# lolo4-rc2.net
KiCad netlist of a schematic drawn in EAGLE
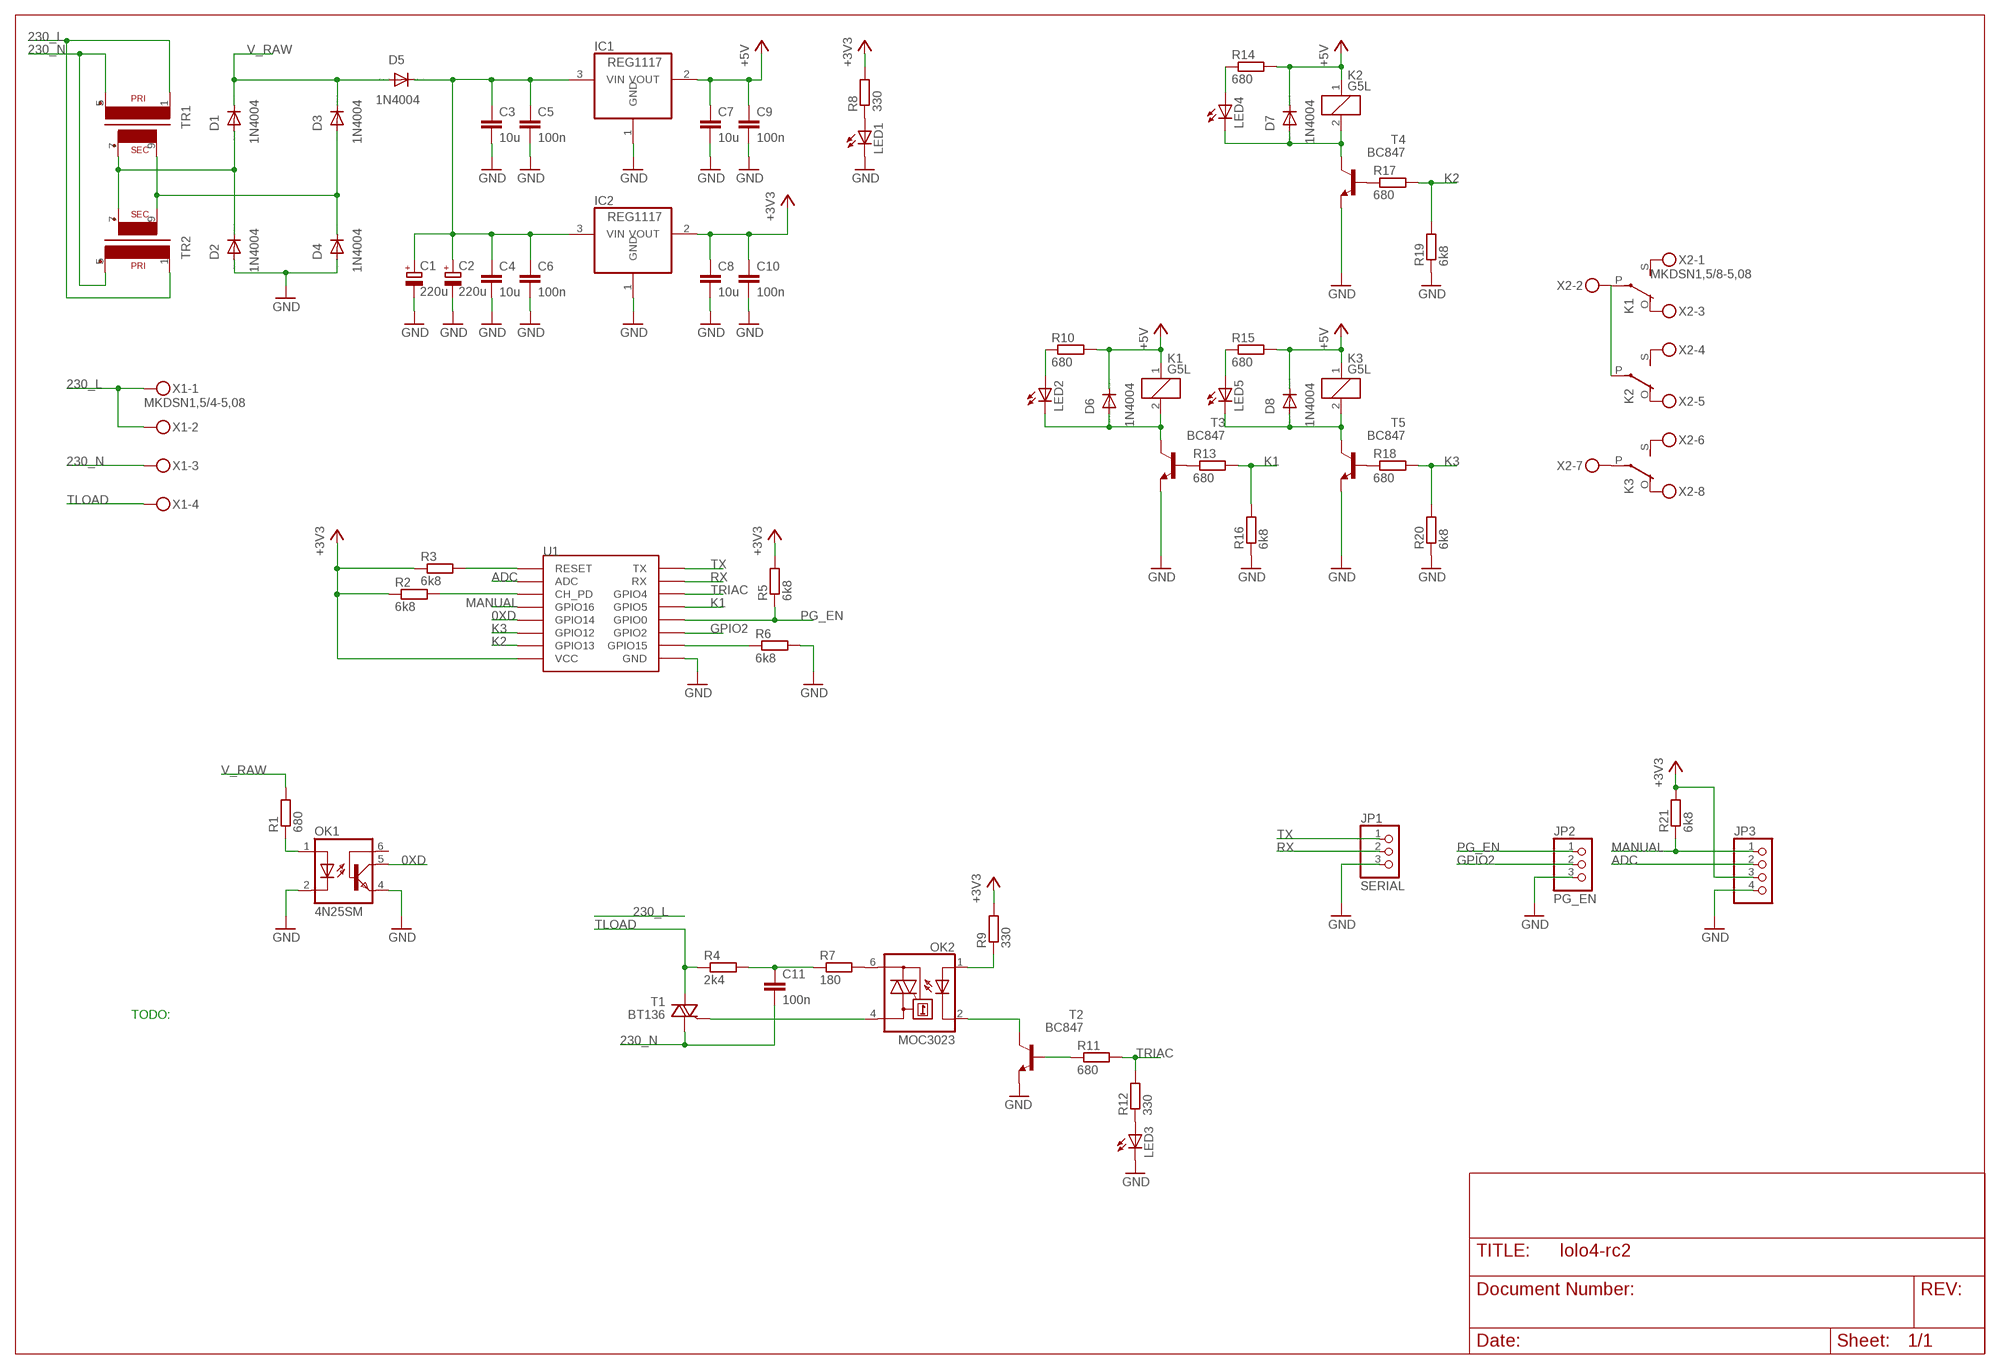
[diagram p0: schematic, sheet 1]

(export (version "E")
  (design (tool "Eeschema 10.0.6"))
  (components
    (comp (ref "C1")
      (value "220u")
      (footprint "eagle-import:SANYO-OSCON_SMD_E7")
      (libsource (lib "eagle-import") (part "CPOL-EUSANYO_SMD_E7"))
    )
    (comp (ref "C2")
      (value "220u")
      (footprint "eagle-import:SANYO-OSCON_SMD_E7")
      (libsource (lib "eagle-import") (part "CPOL-EUSANYO_SMD_E7"))
    )
    (comp (ref "C3")
      (value "10u")
      (footprint "eagle-import:C1206")
      (libsource (lib "eagle-import") (part "resistor_C-EUC1206"))
    )
    (comp (ref "C4")
      (value "10u")
      (footprint "eagle-import:C1206")
      (libsource (lib "eagle-import") (part "resistor_C-EUC1206"))
    )
    (comp (ref "C5")
      (value "100n")
      (footprint "eagle-import:C1206")
      (libsource (lib "eagle-import") (part "resistor_C-EUC1206"))
    )
    (comp (ref "C6")
      (value "100n")
      (footprint "eagle-import:C1206")
      (libsource (lib "eagle-import") (part "resistor_C-EUC1206"))
    )
    (comp (ref "C7")
      (value "10u")
      (footprint "eagle-import:C1206")
      (libsource (lib "eagle-import") (part "resistor_C-EUC1206"))
    )
    (comp (ref "C8")
      (value "10u")
      (footprint "eagle-import:C1206")
      (libsource (lib "eagle-import") (part "resistor_C-EUC1206"))
    )
    (comp (ref "C9")
      (value "100n")
      (footprint "eagle-import:C1206")
      (libsource (lib "eagle-import") (part "resistor_C-EUC1206"))
    )
    (comp (ref "C10")
      (value "100n")
      (footprint "eagle-import:C1206")
      (libsource (lib "eagle-import") (part "resistor_C-EUC1206"))
    )
    (comp (ref "C11")
      (value "100n")
      (footprint "eagle-import:C150-054X183")
      (libsource (lib "eagle-import") (part "C-EU150-054X183"))
    )
    (comp (ref "D1")
      (value "1N4004")
      (footprint "eagle-import:DO41-10")
      (libsource (lib "eagle-import") (part "1N4004"))
    )
    (comp (ref "D2")
      (value "1N4004")
      (footprint "eagle-import:DO41-10")
      (libsource (lib "eagle-import") (part "1N4004"))
    )
    (comp (ref "D3")
      (value "1N4004")
      (footprint "eagle-import:DO41-10")
      (libsource (lib "eagle-import") (part "1N4004"))
    )
    (comp (ref "D4")
      (value "1N4004")
      (footprint "eagle-import:DO41-10")
      (libsource (lib "eagle-import") (part "1N4004"))
    )
    (comp (ref "D5")
      (value "1N4004")
      (footprint "eagle-import:DO41-10")
      (libsource (lib "eagle-import") (part "1N4004"))
    )
    (comp (ref "D6")
      (value "1N4004")
      (footprint "eagle-import:DO41-10")
      (libsource (lib "eagle-import") (part "1N4004"))
    )
    (comp (ref "D7")
      (value "1N4004")
      (footprint "eagle-import:DO41-10")
      (libsource (lib "eagle-import") (part "1N4004"))
    )
    (comp (ref "D8")
      (value "1N4004")
      (footprint "eagle-import:DO41-10")
      (libsource (lib "eagle-import") (part "1N4004"))
    )
    (comp (ref "IC1")
      (value "REG1117")
      (footprint "eagle-import:SOT223")
      (libsource (lib "eagle-import") (part "REG1117"))
    )
    (comp (ref "IC2")
      (value "REG1117")
      (footprint "eagle-import:SOT223")
      (libsource (lib "eagle-import") (part "REG1117"))
    )
    (comp (ref "JP1")
      (value "SERIAL")
      (footprint "eagle-import:1X03")
      (libsource (lib "eagle-import") (part "PINHD-1X3"))
    )
    (comp (ref "JP2")
      (value "PG_EN")
      (footprint "eagle-import:1X03")
      (libsource (lib "eagle-import") (part "PINHD-1X3"))
    )
    (comp (ref "JP3")
      (value "PINHD-1X4")
      (footprint "eagle-import:1X04")
      (libsource (lib "eagle-import") (part "PINHD-1X4"))
    )
    (comp (ref "K1")
      (value "G5L")
      (footprint "eagle-import:G5LE")
      (libsource (lib "eagle-import") (part "G5L"))
    )
    (comp (ref "K2")
      (value "G5L")
      (footprint "eagle-import:G5LE")
      (libsource (lib "eagle-import") (part "G5L"))
    )
    (comp (ref "K3")
      (value "G5L")
      (footprint "eagle-import:G5LE")
      (libsource (lib "eagle-import") (part "G5L"))
    )
    (comp (ref "LED1")
      (value "LEDSML1206")
      (footprint "eagle-import:SML1206")
      (libsource (lib "eagle-import") (part "LEDSML1206"))
    )
    (comp (ref "LED2")
      (value "LEDSML1206")
      (footprint "eagle-import:SML1206")
      (libsource (lib "eagle-import") (part "LEDSML1206"))
    )
    (comp (ref "LED3")
      (value "LEDSML1206")
      (footprint "eagle-import:SML1206")
      (libsource (lib "eagle-import") (part "LEDSML1206"))
    )
    (comp (ref "LED4")
      (value "LEDSML1206")
      (footprint "eagle-import:SML1206")
      (libsource (lib "eagle-import") (part "LEDSML1206"))
    )
    (comp (ref "LED5")
      (value "LEDSML1206")
      (footprint "eagle-import:SML1206")
      (libsource (lib "eagle-import") (part "LEDSML1206"))
    )
    (comp (ref "OK1")
      (value "4N25SM")
      (footprint "eagle-import:DIL6-SMD")
      (fields (field (name "MF") "FAIRCHILD SEMICONDUCTOR"))
      (libsource (lib "eagle-import") (part "4N?MS25"))
    )
    (comp (ref "OK2")
      (value "MOC3023")
      (footprint "eagle-import:DIL6-SMD")
      (fields (field (name "MF") "FAIRCHILD SEMICONDUCTOR") (field (name "MPN") "MOC3031SM"))
      (libsource (lib "eagle-import") (part "MOC30S31"))
    )
    (comp (ref "R1")
      (value "680")
      (footprint "eagle-import:R1206")
      (libsource (lib "eagle-import") (part "R-EU_R1206"))
    )
    (comp (ref "R2")
      (value "6k8")
      (footprint "eagle-import:R1206")
      (libsource (lib "eagle-import") (part "R-EU_R1206"))
    )
    (comp (ref "R3")
      (value "6k8")
      (footprint "eagle-import:R1206")
      (libsource (lib "eagle-import") (part "R-EU_R1206"))
    )
    (comp (ref "R4")
      (value "2k4")
      (footprint "eagle-import:0207_7")
      (libsource (lib "eagle-import") (part "R-EU_0207/7"))
    )
    (comp (ref "R5")
      (value "6k8")
      (footprint "eagle-import:R1206")
      (libsource (lib "eagle-import") (part "R-EU_R1206"))
    )
    (comp (ref "R6")
      (value "6k8")
      (footprint "eagle-import:R1206")
      (libsource (lib "eagle-import") (part "R-EU_R1206"))
    )
    (comp (ref "R7")
      (value "180")
      (footprint "eagle-import:0207_7")
      (libsource (lib "eagle-import") (part "R-EU_0207/7"))
    )
    (comp (ref "R8")
      (value "330")
      (footprint "eagle-import:R1206")
      (libsource (lib "eagle-import") (part "R-EU_R1206"))
    )
    (comp (ref "R9")
      (value "330")
      (footprint "eagle-import:R1206")
      (libsource (lib "eagle-import") (part "R-EU_R1206"))
    )
    (comp (ref "R10")
      (value "680")
      (footprint "eagle-import:R1206")
      (libsource (lib "eagle-import") (part "R-EU_R1206"))
    )
    (comp (ref "R11")
      (value "680")
      (footprint "eagle-import:R1206")
      (libsource (lib "eagle-import") (part "R-EU_R1206"))
    )
    (comp (ref "R12")
      (value "330")
      (footprint "eagle-import:R1206")
      (libsource (lib "eagle-import") (part "R-EU_R1206"))
    )
    (comp (ref "R13")
      (value "680")
      (footprint "eagle-import:R1206")
      (libsource (lib "eagle-import") (part "R-EU_R1206"))
    )
    (comp (ref "R14")
      (value "680")
      (footprint "eagle-import:R1206")
      (libsource (lib "eagle-import") (part "R-EU_R1206"))
    )
    (comp (ref "R15")
      (value "680")
      (footprint "eagle-import:R1206")
      (libsource (lib "eagle-import") (part "R-EU_R1206"))
    )
    (comp (ref "R16")
      (value "6k8")
      (footprint "eagle-import:R1206")
      (libsource (lib "eagle-import") (part "R-EU_R1206"))
    )
    (comp (ref "R17")
      (value "680")
      (footprint "eagle-import:R1206")
      (libsource (lib "eagle-import") (part "R-EU_R1206"))
    )
    (comp (ref "R18")
      (value "680")
      (footprint "eagle-import:R1206")
      (libsource (lib "eagle-import") (part "R-EU_R1206"))
    )
    (comp (ref "R19")
      (value "6k8")
      (footprint "eagle-import:R1206")
      (libsource (lib "eagle-import") (part "R-EU_R1206"))
    )
    (comp (ref "R20")
      (value "6k8")
      (footprint "eagle-import:R1206")
      (libsource (lib "eagle-import") (part "R-EU_R1206"))
    )
    (comp (ref "R21")
      (value "6k8")
      (footprint "eagle-import:R1206")
      (libsource (lib "eagle-import") (part "R-EU_R1206"))
    )
    (comp (ref "T1")
      (value "BT136")
      (footprint "eagle-import:TO220AB")
      (libsource (lib "eagle-import") (part "BT136"))
    )
    (comp (ref "T2")
      (value "BC847")
      (footprint "eagle-import:SOT23")
      (libsource (lib "eagle-import") (part "BC847"))
    )
    (comp (ref "T3")
      (value "BC847")
      (footprint "eagle-import:SOT23")
      (libsource (lib "eagle-import") (part "BC847"))
    )
    (comp (ref "T4")
      (value "BC847")
      (footprint "eagle-import:SOT23")
      (libsource (lib "eagle-import") (part "BC847"))
    )
    (comp (ref "T5")
      (value "BC847")
      (footprint "eagle-import:SOT23")
      (libsource (lib "eagle-import") (part "BC847"))
    )
    (comp (ref "TR1")
      (value "VR11")
      (footprint "eagle-import:VR11")
      (libsource (lib "eagle-import") (part "VR11"))
    )
    (comp (ref "TR2")
      (value "VR11")
      (footprint "eagle-import:VR11")
      (libsource (lib "eagle-import") (part "VR11"))
    )
    (comp (ref "U1")
      (value "ESP12SMD")
      (footprint "eagle-import:ESP12-SMD")
      (libsource (lib "eagle-import") (part "ESP12SMD"))
    )
    (comp (ref "X1")
      (value "MKDSN1,5/4-5,08")
      (footprint "eagle-import:MKDSN1,5_4-5,08")
      (libsource (lib "eagle-import") (part "MKDSN1,5/4-5,08"))
    )
    (comp (ref "X2")
      (value "MKDSN1,5/8-5,08")
      (footprint "eagle-import:MKDSN1,5_8-5,08")
      (libsource (lib "eagle-import") (part "MKDSN1,5/8-5,08"))
    )
  )
  (nets
    (net (code "1") (name "+3V3") (class "Default")
      (node (ref "C10") (pin "1") (pinfunction "1_1") (pintype "passive"))
      (node (ref "C8") (pin "1") (pinfunction "1_1") (pintype "passive"))
      (node (ref "IC2") (pin "2") (pinfunction "VOUT_2") (pintype "output"))
      (node (ref "JP3") (pin "3") (pinfunction "3_3") (pintype "passive"))
      (node (ref "R2") (pin "1") (pinfunction "1_1") (pintype "passive"))
      (node (ref "R21") (pin "2") (pinfunction "2_2") (pintype "passive"))
      (node (ref "R3") (pin "1") (pinfunction "1_1") (pintype "passive"))
      (node (ref "R5") (pin "2") (pinfunction "2_2") (pintype "passive"))
      (node (ref "R8") (pin "2") (pinfunction "2_2") (pintype "passive"))
      (node (ref "R9") (pin "2") (pinfunction "2_2") (pintype "passive"))
      (node (ref "U1") (pin "VCC") (pinfunction "VCC_VCC") (pintype "bidirectional"))
    )
    (net (code "2") (name "+5V") (class "Default")
      (node (ref "C7") (pin "1") (pinfunction "1_1") (pintype "passive"))
      (node (ref "C9") (pin "1") (pinfunction "1_1") (pintype "passive"))
      (node (ref "D6") (pin "C") (pinfunction "C_C") (pintype "passive"))
      (node (ref "D7") (pin "C") (pinfunction "C_C") (pintype "passive"))
      (node (ref "D8") (pin "C") (pinfunction "C_C") (pintype "passive"))
      (node (ref "IC1") (pin "2") (pinfunction "VOUT_2") (pintype "output"))
      (node (ref "K1") (pin "1") (pinfunction "1_1") (pintype "passive"))
      (node (ref "K2") (pin "1") (pinfunction "1_1") (pintype "passive"))
      (node (ref "K3") (pin "1") (pinfunction "1_1") (pintype "passive"))
      (node (ref "R10") (pin "2") (pinfunction "2_2") (pintype "passive"))
      (node (ref "R14") (pin "2") (pinfunction "2_2") (pintype "passive"))
      (node (ref "R15") (pin "2") (pinfunction "2_2") (pintype "passive"))
    )
    (net (code "3") (name "/0XD") (class "Default")
      (node (ref "OK1") (pin "5") (pinfunction "COL_5") (pintype "passive"))
      (node (ref "U1") (pin "GPIO14") (pinfunction "GPIO14_GPIO14") (pintype "bidirectional"))
    )
    (net (code "4") (name "/230_L") (class "Default")
      (node (ref "TR1") (pin "1") (pinfunction "P1_1") (pintype "passive"))
      (node (ref "TR2") (pin "1") (pinfunction "P1_1") (pintype "passive"))
      (node (ref "X1") (pin "1") (pinfunction "KL_1") (pintype "passive"))
      (node (ref "X1") (pin "2") (pinfunction "KL_2") (pintype "passive"))
    )
    (net (code "5") (name "/230_N") (class "Default")
      (node (ref "C11") (pin "2") (pinfunction "2_2") (pintype "passive"))
      (node (ref "T1") (pin "1") (pinfunction "A1_1") (pintype "passive"))
      (node (ref "TR1") (pin "5") (pinfunction "P2_5") (pintype "passive"))
      (node (ref "TR2") (pin "5") (pinfunction "P2_5") (pintype "passive"))
      (node (ref "X1") (pin "3") (pinfunction "KL_3") (pintype "passive"))
    )
    (net (code "6") (name "/ADC") (class "Default")
      (node (ref "JP3") (pin "2") (pinfunction "2_2") (pintype "passive"))
      (node (ref "U1") (pin "ADC") (pinfunction "ADC_ADC") (pintype "bidirectional"))
    )
    (net (code "7") (name "/GPIO2") (class "Default")
      (node (ref "JP2") (pin "2") (pinfunction "2_2") (pintype "passive"))
      (node (ref "U1") (pin "GPIO2") (pinfunction "GPIO2_GPIO2") (pintype "bidirectional"))
    )
    (net (code "8") (name "/K1") (class "Default")
      (node (ref "R13") (pin "2") (pinfunction "2_2") (pintype "passive"))
      (node (ref "R16") (pin "2") (pinfunction "2_2") (pintype "passive"))
      (node (ref "U1") (pin "GPIO5") (pinfunction "GPIO5_GPIO5") (pintype "bidirectional"))
    )
    (net (code "9") (name "/K2") (class "Default")
      (node (ref "R17") (pin "2") (pinfunction "2_2") (pintype "passive"))
      (node (ref "R19") (pin "2") (pinfunction "2_2") (pintype "passive"))
      (node (ref "U1") (pin "GPIO13") (pinfunction "GPIO13_GPIO13") (pintype "bidirectional"))
    )
    (net (code "10") (name "/K3") (class "Default")
      (node (ref "R18") (pin "2") (pinfunction "2_2") (pintype "passive"))
      (node (ref "R20") (pin "2") (pinfunction "2_2") (pintype "passive"))
      (node (ref "U1") (pin "GPIO12") (pinfunction "GPIO12_GPIO12") (pintype "bidirectional"))
    )
    (net (code "11") (name "/MANUAL") (class "Default")
      (node (ref "JP3") (pin "1") (pinfunction "1_1") (pintype "passive"))
      (node (ref "R21") (pin "1") (pinfunction "1_1") (pintype "passive"))
      (node (ref "U1") (pin "GPIO16") (pinfunction "GPIO16_GPIO16") (pintype "bidirectional"))
    )
    (net (code "12") (name "/PG_EN") (class "Default")
      (node (ref "JP2") (pin "1") (pinfunction "1_1") (pintype "passive"))
      (node (ref "R5") (pin "1") (pinfunction "1_1") (pintype "passive"))
      (node (ref "U1") (pin "GPIO0") (pinfunction "GPIO0_GPIO0") (pintype "bidirectional"))
    )
    (net (code "13") (name "/RX") (class "Default")
      (node (ref "JP1") (pin "2") (pinfunction "2_2") (pintype "passive"))
      (node (ref "U1") (pin "RXD0") (pinfunction "RX_RXD0") (pintype "bidirectional"))
    )
    (net (code "14") (name "/TLOAD") (class "Default")
      (node (ref "R4") (pin "1") (pinfunction "1_1") (pintype "passive"))
      (node (ref "T1") (pin "2") (pinfunction "A2_2") (pintype "passive"))
      (node (ref "X1") (pin "4") (pinfunction "KL_4") (pintype "passive"))
    )
    (net (code "15") (name "/TRIAC") (class "Default")
      (node (ref "R11") (pin "2") (pinfunction "2_2") (pintype "passive"))
      (node (ref "R12") (pin "2") (pinfunction "2_2") (pintype "passive"))
      (node (ref "U1") (pin "GPIO4") (pinfunction "GPIO4_GPIO4") (pintype "bidirectional"))
    )
    (net (code "16") (name "/TX") (class "Default")
      (node (ref "JP1") (pin "1") (pinfunction "1_1") (pintype "passive"))
      (node (ref "U1") (pin "TXD0") (pinfunction "TX_TXD0") (pintype "bidirectional"))
    )
    (net (code "17") (name "/V_RAW") (class "Default")
      (node (ref "D1") (pin "C") (pinfunction "C_C") (pintype "passive"))
      (node (ref "D3") (pin "C") (pinfunction "C_C") (pintype "passive"))
      (node (ref "D5") (pin "A") (pinfunction "A_A") (pintype "passive"))
      (node (ref "R1") (pin "2") (pinfunction "2_2") (pintype "passive"))
    )
    (net (code "18") (name "GND") (class "Default")
      (node (ref "C1") (pin "-") (pinfunction "-_-") (pintype "passive"))
      (node (ref "C10") (pin "2") (pinfunction "2_2") (pintype "passive"))
      (node (ref "C2") (pin "-") (pinfunction "-_-") (pintype "passive"))
      (node (ref "C3") (pin "2") (pinfunction "2_2") (pintype "passive"))
      (node (ref "C4") (pin "2") (pinfunction "2_2") (pintype "passive"))
      (node (ref "C5") (pin "2") (pinfunction "2_2") (pintype "passive"))
      (node (ref "C6") (pin "2") (pinfunction "2_2") (pintype "passive"))
      (node (ref "C7") (pin "2") (pinfunction "2_2") (pintype "passive"))
      (node (ref "C8") (pin "2") (pinfunction "2_2") (pintype "passive"))
      (node (ref "C9") (pin "2") (pinfunction "2_2") (pintype "passive"))
      (node (ref "D2") (pin "A") (pinfunction "A_A") (pintype "passive"))
      (node (ref "D4") (pin "A") (pinfunction "A_A") (pintype "passive"))
      (node (ref "IC1") (pin "1") (pinfunction "GND_1") (pintype "power_in"))
      (node (ref "IC2") (pin "1") (pinfunction "GND_1") (pintype "power_in"))
      (node (ref "JP1") (pin "3") (pinfunction "3_3") (pintype "passive"))
      (node (ref "JP2") (pin "3") (pinfunction "3_3") (pintype "passive"))
      (node (ref "JP3") (pin "4") (pinfunction "4_4") (pintype "passive"))
      (node (ref "LED1") (pin "C") (pinfunction "C_C") (pintype "passive"))
      (node (ref "LED3") (pin "C") (pinfunction "C_C") (pintype "passive"))
      (node (ref "OK1") (pin "2") (pinfunction "C_2") (pintype "passive"))
      (node (ref "OK1") (pin "4") (pinfunction "EMI_4") (pintype "passive"))
      (node (ref "R16") (pin "1") (pinfunction "1_1") (pintype "passive"))
      (node (ref "R19") (pin "1") (pinfunction "1_1") (pintype "passive"))
      (node (ref "R20") (pin "1") (pinfunction "1_1") (pintype "passive"))
      (node (ref "R6") (pin "2") (pinfunction "2_2") (pintype "passive"))
      (node (ref "T2") (pin "2") (pinfunction "E_2") (pintype "passive"))
      (node (ref "T3") (pin "2") (pinfunction "E_2") (pintype "passive"))
      (node (ref "T4") (pin "2") (pinfunction "E_2") (pintype "passive"))
      (node (ref "T5") (pin "2") (pinfunction "E_2") (pintype "passive"))
      (node (ref "U1") (pin "GND") (pinfunction "GND_GND") (pintype "bidirectional"))
    )
    (net (code "19") (name "Net-(C11-Pad1)") (class "Default")
      (node (ref "C11") (pin "1") (pinfunction "1_1") (pintype "passive"))
      (node (ref "R4") (pin "2") (pinfunction "2_2") (pintype "passive"))
      (node (ref "R7") (pin "1") (pinfunction "1_1") (pintype "passive"))
    )
    (net (code "20") (name "Net-(IC1-VIN)") (class "Default")
      (node (ref "C1") (pin "+") (pinfunction "+_+") (pintype "passive"))
      (node (ref "C2") (pin "+") (pinfunction "+_+") (pintype "passive"))
      (node (ref "C3") (pin "1") (pinfunction "1_1") (pintype "passive"))
      (node (ref "C4") (pin "1") (pinfunction "1_1") (pintype "passive"))
      (node (ref "C5") (pin "1") (pinfunction "1_1") (pintype "passive"))
      (node (ref "C6") (pin "1") (pinfunction "1_1") (pintype "passive"))
      (node (ref "D5") (pin "C") (pinfunction "C_C") (pintype "passive"))
      (node (ref "IC1") (pin "3") (pinfunction "VIN_3") (pintype "input"))
      (node (ref "IC2") (pin "3") (pinfunction "VIN_3") (pintype "input"))
    )
    (net (code "21") (name "Net-(LED1-PadA)") (class "Default")
      (node (ref "LED1") (pin "A") (pinfunction "A_A") (pintype "passive"))
      (node (ref "R8") (pin "1") (pinfunction "1_1") (pintype "passive"))
    )
    (net (code "22") (name "Net-(LED2-PadA)") (class "Default")
      (node (ref "LED2") (pin "A") (pinfunction "A_A") (pintype "passive"))
      (node (ref "R10") (pin "1") (pinfunction "1_1") (pintype "passive"))
    )
    (net (code "23") (name "Net-(LED3-PadA)") (class "Default")
      (node (ref "LED3") (pin "A") (pinfunction "A_A") (pintype "passive"))
      (node (ref "R12") (pin "1") (pinfunction "1_1") (pintype "passive"))
    )
    (net (code "24") (name "Net-(LED4-PadA)") (class "Default")
      (node (ref "LED4") (pin "A") (pinfunction "A_A") (pintype "passive"))
      (node (ref "R14") (pin "1") (pinfunction "1_1") (pintype "passive"))
    )
    (net (code "25") (name "Net-(LED5-PadA)") (class "Default")
      (node (ref "LED5") (pin "A") (pinfunction "A_A") (pintype "passive"))
      (node (ref "R15") (pin "1") (pinfunction "1_1") (pintype "passive"))
    )
    (net (code "26") (name "Net-(OK1-A)") (class "Default")
      (node (ref "OK1") (pin "1") (pinfunction "A_1") (pintype "passive"))
      (node (ref "R1") (pin "1") (pinfunction "1_1") (pintype "passive"))
    )
    (net (code "27") (name "Net-(OK2-A)") (class "Default")
      (node (ref "OK2") (pin "1") (pinfunction "A_1") (pintype "passive"))
      (node (ref "R9") (pin "1") (pinfunction "1_1") (pintype "passive"))
    )
    (net (code "28") (name "Net-(OK2-A1)") (class "Default")
      (node (ref "OK2") (pin "4") (pinfunction "A1_4") (pintype "passive"))
      (node (ref "T1") (pin "3") (pinfunction "G_3") (pintype "passive"))
    )
    (net (code "29") (name "Net-(OK2-A2)") (class "Default")
      (node (ref "OK2") (pin "6") (pinfunction "A2_6") (pintype "passive"))
      (node (ref "R7") (pin "2") (pinfunction "2_2") (pintype "passive"))
    )
    (net (code "30") (name "Net-(OK2-C)") (class "Default")
      (node (ref "OK2") (pin "2") (pinfunction "C_2") (pintype "passive"))
      (node (ref "T2") (pin "3") (pinfunction "C_3") (pintype "passive"))
    )
    (net (code "31") (name "Net-(R2-Pad2)") (class "Default")
      (node (ref "R2") (pin "2") (pinfunction "2_2") (pintype "passive"))
      (node (ref "U1") (pin "CH_PD") (pinfunction "CH_PD_CH_PD") (pintype "bidirectional"))
    )
    (net (code "32") (name "Net-(R3-Pad2)") (class "Default")
      (node (ref "R3") (pin "2") (pinfunction "2_2") (pintype "passive"))
      (node (ref "U1") (pin "RESET") (pinfunction "RESET_RESET") (pintype "bidirectional"))
    )
    (net (code "33") (name "Net-(R6-Pad1)") (class "Default")
      (node (ref "R6") (pin "1") (pinfunction "1_1") (pintype "passive"))
      (node (ref "U1") (pin "GPIO15") (pinfunction "GPIO15_GPIO15") (pintype "bidirectional"))
    )
    (net (code "34") (name "Net-(T2-B)") (class "Default")
      (node (ref "R11") (pin "1") (pinfunction "1_1") (pintype "passive"))
      (node (ref "T2") (pin "1") (pinfunction "B_1") (pintype "passive"))
    )
    (net (code "35") (name "Net-(T3-B)") (class "Default")
      (node (ref "R13") (pin "1") (pinfunction "1_1") (pintype "passive"))
      (node (ref "T3") (pin "1") (pinfunction "B_1") (pintype "passive"))
    )
    (net (code "36") (name "Net-(T3-C)") (class "Default")
      (node (ref "D6") (pin "A") (pinfunction "A_A") (pintype "passive"))
      (node (ref "K1") (pin "2") (pinfunction "2_2") (pintype "passive"))
      (node (ref "LED2") (pin "C") (pinfunction "C_C") (pintype "passive"))
      (node (ref "T3") (pin "3") (pinfunction "C_3") (pintype "passive"))
    )
    (net (code "37") (name "Net-(T4-B)") (class "Default")
      (node (ref "R17") (pin "1") (pinfunction "1_1") (pintype "passive"))
      (node (ref "T4") (pin "1") (pinfunction "B_1") (pintype "passive"))
    )
    (net (code "38") (name "Net-(T4-C)") (class "Default")
      (node (ref "D7") (pin "A") (pinfunction "A_A") (pintype "passive"))
      (node (ref "K2") (pin "2") (pinfunction "2_2") (pintype "passive"))
      (node (ref "LED4") (pin "C") (pinfunction "C_C") (pintype "passive"))
      (node (ref "T4") (pin "3") (pinfunction "C_3") (pintype "passive"))
    )
    (net (code "39") (name "Net-(T5-B)") (class "Default")
      (node (ref "R18") (pin "1") (pinfunction "1_1") (pintype "passive"))
      (node (ref "T5") (pin "1") (pinfunction "B_1") (pintype "passive"))
    )
    (net (code "40") (name "Net-(T5-C)") (class "Default")
      (node (ref "D8") (pin "A") (pinfunction "A_A") (pintype "passive"))
      (node (ref "K3") (pin "2") (pinfunction "2_2") (pintype "passive"))
      (node (ref "LED5") (pin "C") (pinfunction "C_C") (pintype "passive"))
      (node (ref "T5") (pin "3") (pinfunction "C_3") (pintype "passive"))
    )
    (net (code "41") (name "Net-(TR1-S3)") (class "Default")
      (node (ref "D1") (pin "A") (pinfunction "A_A") (pintype "passive"))
      (node (ref "D2") (pin "C") (pinfunction "C_C") (pintype "passive"))
      (node (ref "TR1") (pin "7") (pinfunction "S3_7") (pintype "passive"))
      (node (ref "TR2") (pin "7") (pinfunction "S3_7") (pintype "passive"))
    )
    (net (code "42") (name "Net-(TR1-S4)") (class "Default")
      (node (ref "D3") (pin "A") (pinfunction "A_A") (pintype "passive"))
      (node (ref "D4") (pin "C") (pinfunction "C_C") (pintype "passive"))
      (node (ref "TR1") (pin "9") (pinfunction "S4_9") (pintype "passive"))
      (node (ref "TR2") (pin "9") (pinfunction "S4_9") (pintype "passive"))
    )
    (net (code "43") (name "Net-(X2A-KL)") (class "Default")
      (node (ref "K1") (pin "S") (pinfunction "S_S") (pintype "passive"))
      (node (ref "X2") (pin "1") (pinfunction "KL_1") (pintype "passive"))
    )
    (net (code "44") (name "Net-(X2B-KL)") (class "Default")
      (node (ref "K1") (pin "P") (pinfunction "P_P") (pintype "passive"))
      (node (ref "K2") (pin "P") (pinfunction "P_P") (pintype "passive"))
      (node (ref "X2") (pin "2") (pinfunction "KL_2") (pintype "passive"))
    )
    (net (code "45") (name "Net-(X2C-KL)") (class "Default")
      (node (ref "K1") (pin "O") (pinfunction "O_O") (pintype "passive"))
      (node (ref "X2") (pin "3") (pinfunction "KL_3") (pintype "passive"))
    )
    (net (code "46") (name "Net-(X2D-KL)") (class "Default")
      (node (ref "K2") (pin "S") (pinfunction "S_S") (pintype "passive"))
      (node (ref "X2") (pin "4") (pinfunction "KL_4") (pintype "passive"))
    )
    (net (code "47") (name "Net-(X2E-KL)") (class "Default")
      (node (ref "K2") (pin "O") (pinfunction "O_O") (pintype "passive"))
      (node (ref "X2") (pin "5") (pinfunction "KL_5") (pintype "passive"))
    )
    (net (code "48") (name "Net-(X2F-KL)") (class "Default")
      (node (ref "K3") (pin "S") (pinfunction "S_S") (pintype "passive"))
      (node (ref "X2") (pin "6") (pinfunction "KL_6") (pintype "passive"))
    )
    (net (code "49") (name "Net-(X2G-KL)") (class "Default")
      (node (ref "K3") (pin "P") (pinfunction "P_P") (pintype "passive"))
      (node (ref "X2") (pin "7") (pinfunction "KL_7") (pintype "passive"))
    )
    (net (code "50") (name "Net-(X2H-KL)") (class "Default")
      (node (ref "K3") (pin "O") (pinfunction "O_O") (pintype "passive"))
      (node (ref "X2") (pin "8") (pinfunction "KL_8") (pintype "passive"))
    )
    (net (code "51") (name "unconnected-(OK1-BAS-Pad6)") (class "Default")
      (node (ref "OK1") (pin "6") (pinfunction "BAS_6") (pintype "passive"))
    )
  )
)
